# attenuator_evb.net
KiCad netlist of a schematic drawn in EasyEDA Pro
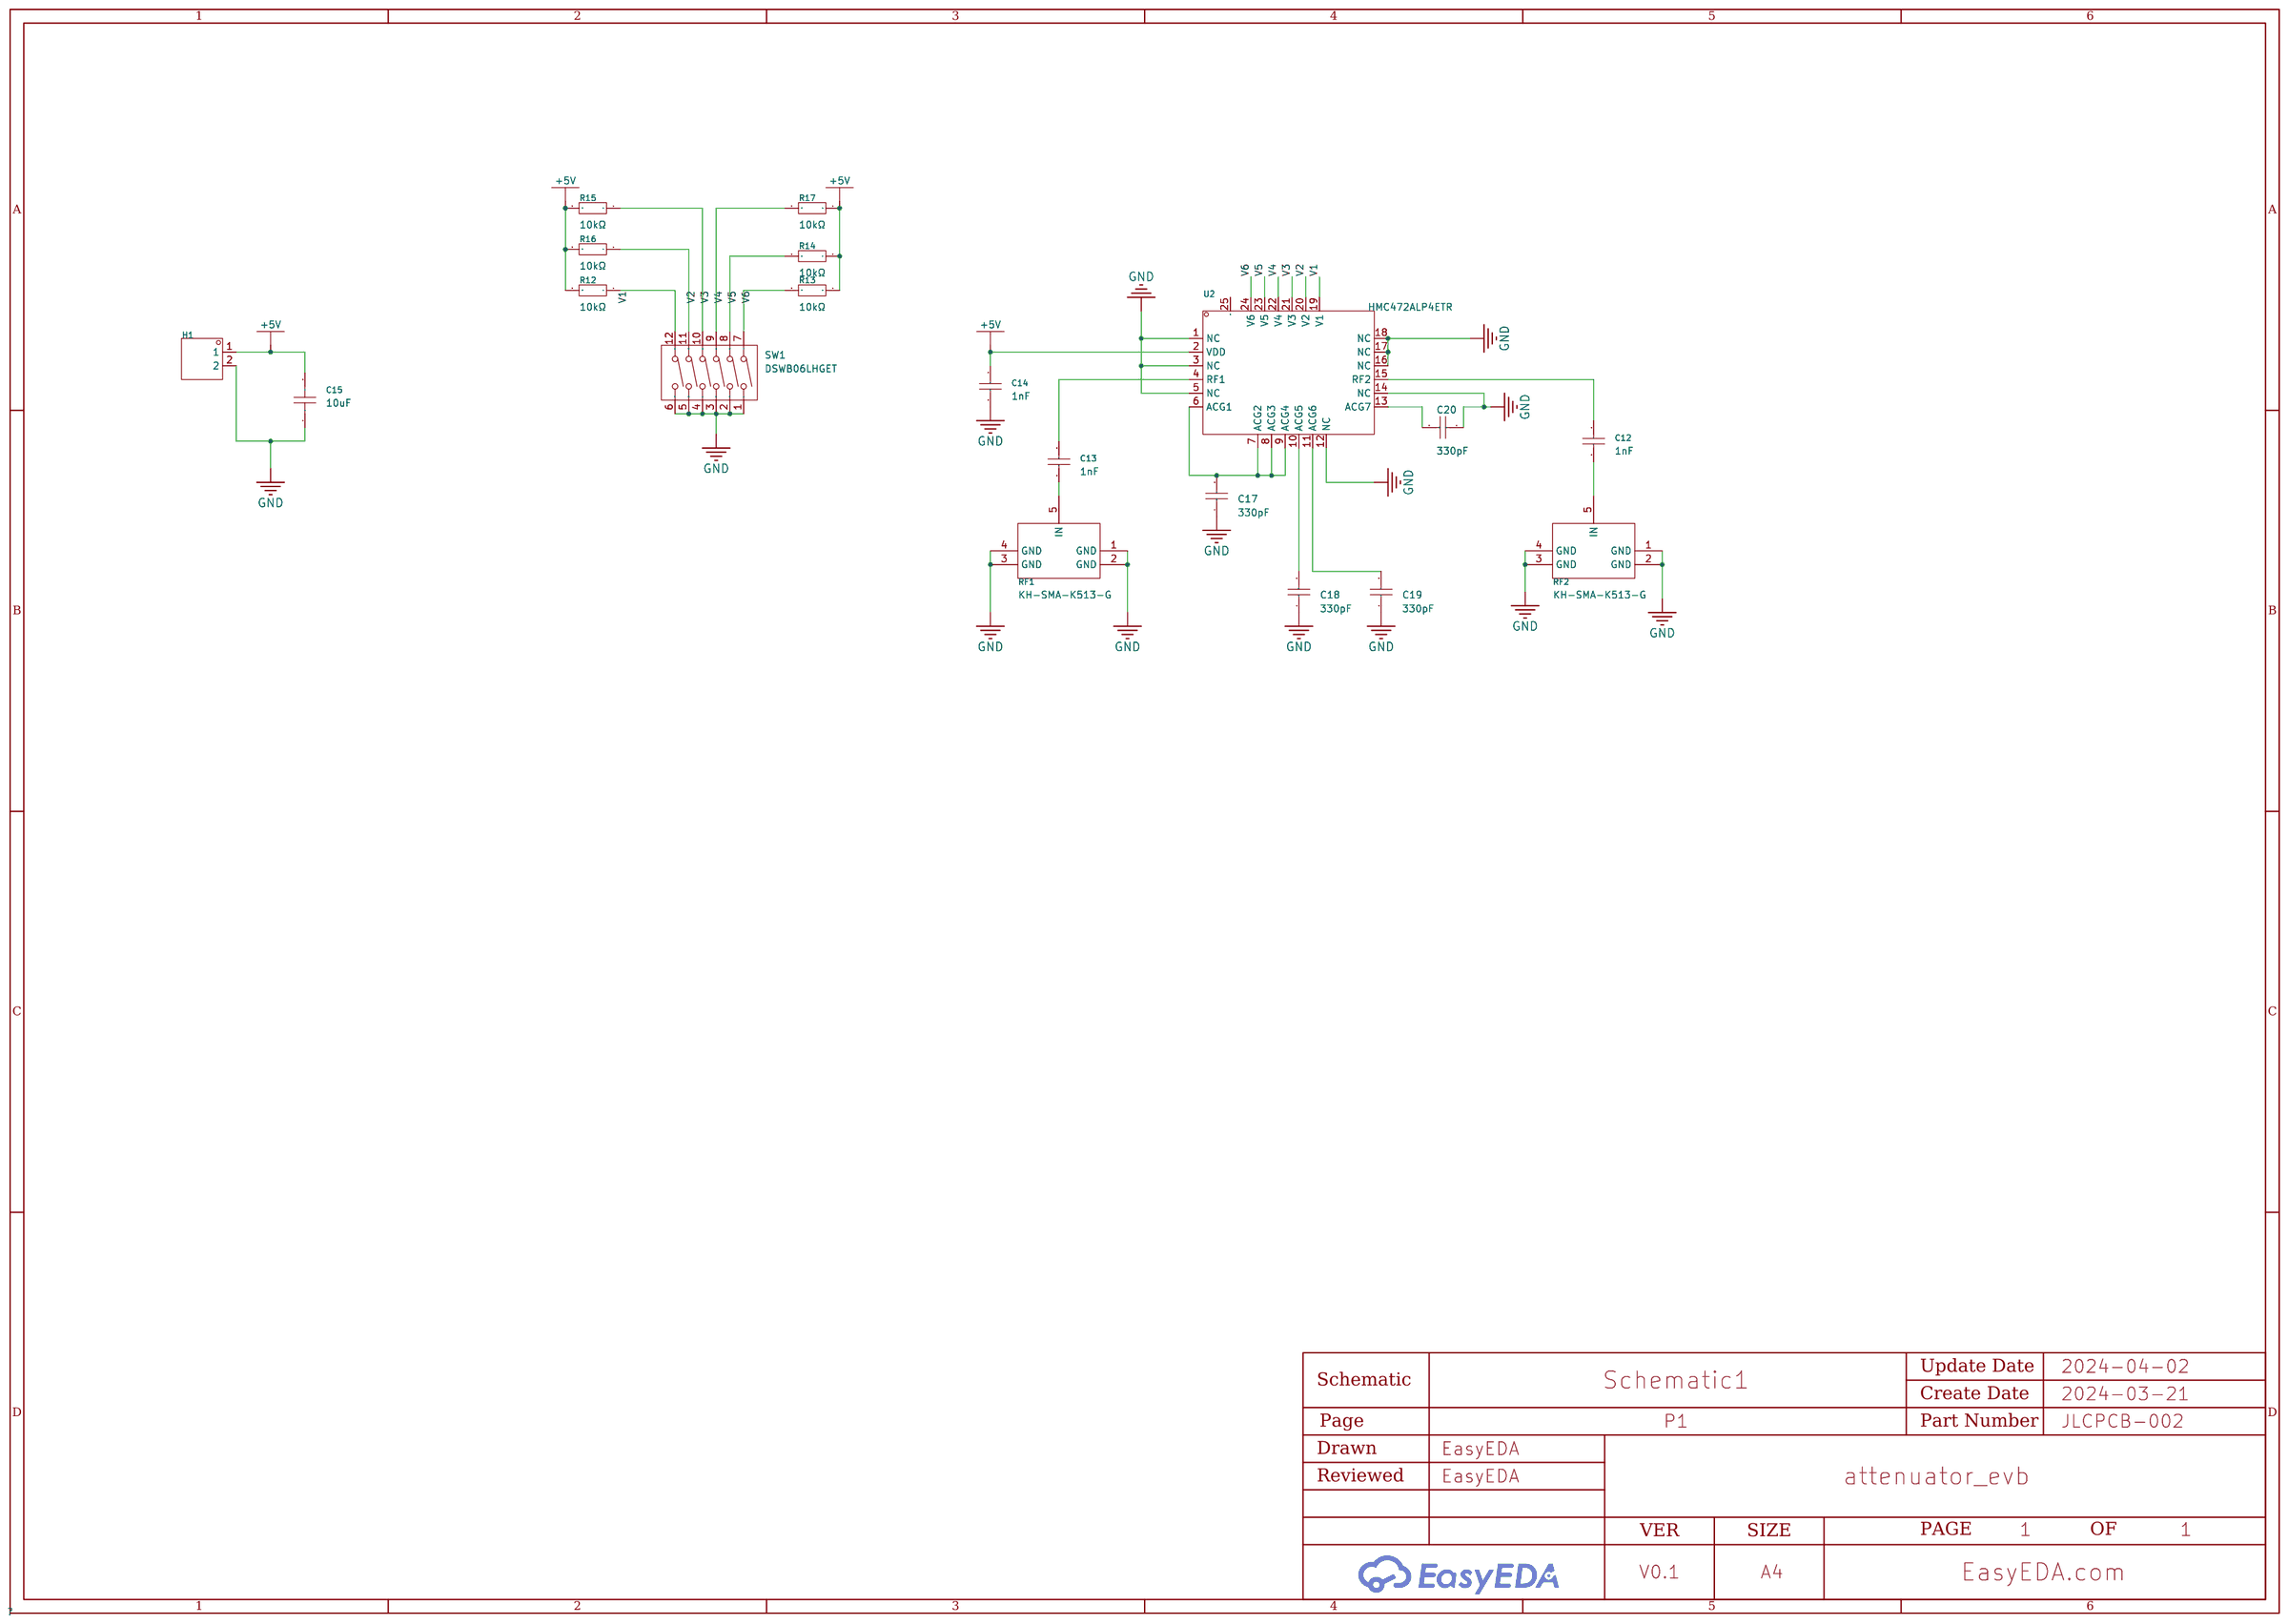
[diagram p0: schematic sheet]

(export (version "E")
  (design (tool "Eeschema 10.0.6"))
  (components
    (comp (ref "C12")
      (value "1nF")
      (footprint "easyedapro:C0402")
      (fields
        (field (name "Manufacturer Part") "CC0402KRX7R9BB102")
        (field (name "Manufacturer") "YAGEO(国巨)")
      )
      (libsource (lib "easyedapro") (part "CC0402KRX7R9BB102"))
    )
    (comp (ref "C13")
      (value "1nF")
      (footprint "easyedapro:C0402")
      (fields
        (field (name "Manufacturer Part") "CC0402KRX7R9BB102")
        (field (name "Manufacturer") "YAGEO(国巨)")
      )
      (libsource (lib "easyedapro") (part "CC0402KRX7R9BB102"))
    )
    (comp (ref "C14")
      (value "1nF")
      (footprint "easyedapro:C0402")
      (fields
        (field (name "Manufacturer Part") "CC0402KRX7R9BB102")
        (field (name "Manufacturer") "YAGEO(国巨)")
      )
      (libsource (lib "easyedapro") (part "CC0402KRX7R9BB102"))
    )
    (comp (ref "C15")
      (value "10uF")
      (footprint "easyedapro:C0603")
      (fields
        (field (name "Manufacturer Part") "CL10A106MP8NNNC")
        (field (name "Manufacturer") "SAMSUNG(三星)")
      )
      (libsource (lib "easyedapro") (part "CL10A106MP8NNNC"))
    )
    (comp (ref "C17")
      (value "330pF")
      (footprint "easyedapro:C0603")
      (fields (field (name "Manufacturer Part") "0603B331K500NT") (field (name "Manufacturer") "FH(风华)"))
      (libsource (lib "easyedapro") (part "0603B331K500NT"))
    )
    (comp (ref "C18")
      (value "330pF")
      (footprint "easyedapro:C0603")
      (fields (field (name "Manufacturer Part") "0603B331K500NT") (field (name "Manufacturer") "FH(风华)"))
      (libsource (lib "easyedapro") (part "0603B331K500NT"))
    )
    (comp (ref "C19")
      (value "330pF")
      (footprint "easyedapro:C0603")
      (fields (field (name "Manufacturer Part") "0603B331K500NT") (field (name "Manufacturer") "FH(风华)"))
      (libsource (lib "easyedapro") (part "0603B331K500NT"))
    )
    (comp (ref "C20")
      (value "330pF")
      (footprint "easyedapro:C0603")
      (fields (field (name "Manufacturer Part") "0603B331K500NT") (field (name "Manufacturer") "FH(风华)"))
      (libsource (lib "easyedapro") (part "0603B331K500NT"))
    )
    (comp (ref "H1")
      (value "~")
      (footprint "easyedapro:HDR-TH_2P-P2.54-V-M-1")
      (libsource (lib "easyedapro") (part "210S-1*2P L=11.6MMGold-plated black"))
    )
    (comp (ref "R12")
      (value "10kΩ")
      (footprint "easyedapro:R0603")
      (fields
        (field (name "Manufacturer Part") "0603WAF1002T5E")
        (field (name "Manufacturer") "UNI-ROYAL(厚声)")
      )
      (libsource (lib "easyedapro") (part "0603WAF1002T5E"))
    )
    (comp (ref "R13")
      (value "10kΩ")
      (footprint "easyedapro:R0603")
      (fields
        (field (name "Manufacturer Part") "0603WAF1002T5E")
        (field (name "Manufacturer") "UNI-ROYAL(厚声)")
      )
      (libsource (lib "easyedapro") (part "0603WAF1002T5E"))
    )
    (comp (ref "R14")
      (value "10kΩ")
      (footprint "easyedapro:R0603")
      (fields
        (field (name "Manufacturer Part") "0603WAF1002T5E")
        (field (name "Manufacturer") "UNI-ROYAL(厚声)")
      )
      (libsource (lib "easyedapro") (part "0603WAF1002T5E"))
    )
    (comp (ref "R15")
      (value "10kΩ")
      (footprint "easyedapro:R0603")
      (fields
        (field (name "Manufacturer Part") "0603WAF1002T5E")
        (field (name "Manufacturer") "UNI-ROYAL(厚声)")
      )
      (libsource (lib "easyedapro") (part "0603WAF1002T5E"))
    )
    (comp (ref "R16")
      (value "10kΩ")
      (footprint "easyedapro:R0603")
      (fields
        (field (name "Manufacturer Part") "0603WAF1002T5E")
        (field (name "Manufacturer") "UNI-ROYAL(厚声)")
      )
      (libsource (lib "easyedapro") (part "0603WAF1002T5E"))
    )
    (comp (ref "R17")
      (value "10kΩ")
      (footprint "easyedapro:R0603")
      (fields
        (field (name "Manufacturer Part") "0603WAF1002T5E")
        (field (name "Manufacturer") "UNI-ROYAL(厚声)")
      )
      (libsource (lib "easyedapro") (part "0603WAF1002T5E"))
    )
    (comp (ref "RF1")
      (value "KH-SMA-K513-G")
      (footprint "easyedapro:ANT-TH_KH-SMA-K513-G")
      (fields (field (name "Manufacturer") "kinghelm(金航标)"))
      (libsource (lib "easyedapro") (part "KH-SMA-K513-G"))
    )
    (comp (ref "RF2")
      (value "KH-SMA-K513-G")
      (footprint "easyedapro:ANT-TH_KH-SMA-K513-G")
      (fields (field (name "Manufacturer") "kinghelm(金航标)"))
      (libsource (lib "easyedapro") (part "KH-SMA-K513-G"))
    )
    (comp (ref "SW1")
      (value "DSWB06LHGET")
      (footprint "easyedapro:SW-TH_DSWB06LHGET")
      (description "Type:平拨,凸起式 Circuit:SPST Number of Positions:6Bit Lead Pitch:2.54mm Operating Life:- Color:Red")
      (fields (field (name "Manufacturer") "YE"))
      (libsource (lib "easyedapro") (part "DSWB06LHGET"))
    )
    (comp (ref "U2")
      (value "HMC472ALP4ETR")
      (footprint "easyedapro:QFN-24_L4.0-W4.0-P0.50-TL-EP2.7")
      (fields (field (name "Manufacturer") "ADI(亚德诺)"))
      (libsource (lib "easyedapro") (part "HMC472ALP4ETR"))
    )
  )
  (nets
    (net (code "1") (name "+5V") (class "Default")
      (node (ref "C14") (pin "2") (pinfunction "2_2") (pintype "input"))
      (node (ref "C15") (pin "2") (pinfunction "2_2") (pintype "input"))
      (node (ref "H1") (pin "1") (pinfunction "1_1") (pintype "input"))
      (node (ref "R12") (pin "2") (pinfunction "2_2") (pintype "input"))
      (node (ref "R13") (pin "1") (pinfunction "1_1") (pintype "input"))
      (node (ref "R14") (pin "1") (pinfunction "1_1") (pintype "input"))
      (node (ref "R15") (pin "2") (pinfunction "2_2") (pintype "input"))
      (node (ref "R16") (pin "2") (pinfunction "2_2") (pintype "input"))
      (node (ref "R17") (pin "1") (pinfunction "1_1") (pintype "input"))
      (node (ref "U2") (pin "2") (pinfunction "VDD_2") (pintype "input"))
    )
    (net (code "2") (name "/V1") (class "Default")
      (node (ref "R12") (pin "1") (pinfunction "1_1") (pintype "input"))
      (node (ref "SW1") (pin "12") (pinfunction "12_12") (pintype "unspecified"))
      (node (ref "U2") (pin "19") (pinfunction "V1_19") (pintype "input"))
    )
    (net (code "3") (name "/V2") (class "Default")
      (node (ref "R16") (pin "1") (pinfunction "1_1") (pintype "input"))
      (node (ref "SW1") (pin "11") (pinfunction "11_11") (pintype "unspecified"))
      (node (ref "U2") (pin "20") (pinfunction "V2_20") (pintype "input"))
    )
    (net (code "4") (name "/V3") (class "Default")
      (node (ref "R15") (pin "1") (pinfunction "1_1") (pintype "input"))
      (node (ref "SW1") (pin "10") (pinfunction "10_10") (pintype "unspecified"))
      (node (ref "U2") (pin "21") (pinfunction "V3_21") (pintype "input"))
    )
    (net (code "5") (name "/V4") (class "Default")
      (node (ref "R17") (pin "2") (pinfunction "2_2") (pintype "input"))
      (node (ref "SW1") (pin "9") (pinfunction "9_9") (pintype "unspecified"))
      (node (ref "U2") (pin "22") (pinfunction "V4_22") (pintype "input"))
    )
    (net (code "6") (name "/V5") (class "Default")
      (node (ref "R14") (pin "2") (pinfunction "2_2") (pintype "input"))
      (node (ref "SW1") (pin "8") (pinfunction "8_8") (pintype "unspecified"))
      (node (ref "U2") (pin "23") (pinfunction "V5_23") (pintype "input"))
    )
    (net (code "7") (name "/V6") (class "Default")
      (node (ref "R13") (pin "2") (pinfunction "2_2") (pintype "input"))
      (node (ref "SW1") (pin "7") (pinfunction "7_7") (pintype "unspecified"))
      (node (ref "U2") (pin "24") (pinfunction "V6_24") (pintype "input"))
    )
    (net (code "8") (name "GND") (class "Default")
      (node (ref "C14") (pin "1") (pinfunction "1_1") (pintype "input"))
      (node (ref "C15") (pin "1") (pinfunction "1_1") (pintype "input"))
      (node (ref "C17") (pin "1") (pinfunction "1_1") (pintype "input"))
      (node (ref "C18") (pin "1") (pinfunction "1_1") (pintype "input"))
      (node (ref "C19") (pin "1") (pinfunction "1_1") (pintype "input"))
      (node (ref "C20") (pin "1") (pinfunction "1_1") (pintype "input"))
      (node (ref "H1") (pin "2") (pinfunction "2_2") (pintype "input"))
      (node (ref "RF1") (pin "1") (pinfunction "GND_1") (pintype "input"))
      (node (ref "RF1") (pin "2") (pinfunction "GND_2") (pintype "input"))
      (node (ref "RF1") (pin "3") (pinfunction "GND_3") (pintype "input"))
      (node (ref "RF1") (pin "4") (pinfunction "GND_4") (pintype "input"))
      (node (ref "RF2") (pin "1") (pinfunction "GND_1") (pintype "input"))
      (node (ref "RF2") (pin "2") (pinfunction "GND_2") (pintype "input"))
      (node (ref "RF2") (pin "3") (pinfunction "GND_3") (pintype "input"))
      (node (ref "RF2") (pin "4") (pinfunction "GND_4") (pintype "input"))
      (node (ref "SW1") (pin "1") (pinfunction "1_1") (pintype "unspecified"))
      (node (ref "SW1") (pin "2") (pinfunction "2_2") (pintype "unspecified"))
      (node (ref "SW1") (pin "3") (pinfunction "3_3") (pintype "unspecified"))
      (node (ref "SW1") (pin "4") (pinfunction "4_4") (pintype "unspecified"))
      (node (ref "SW1") (pin "5") (pinfunction "5_5") (pintype "unspecified"))
      (node (ref "SW1") (pin "6") (pinfunction "6_6") (pintype "unspecified"))
      (node (ref "U2") (pin "1") (pinfunction "NC_1") (pintype "input"))
      (node (ref "U2") (pin "12") (pinfunction "NC_12") (pintype "input"))
      (node (ref "U2") (pin "14") (pinfunction "NC_14") (pintype "input"))
      (node (ref "U2") (pin "16") (pinfunction "NC_16") (pintype "input"))
      (node (ref "U2") (pin "17") (pinfunction "NC_17") (pintype "input"))
      (node (ref "U2") (pin "18") (pinfunction "NC_18") (pintype "input"))
      (node (ref "U2") (pin "3") (pinfunction "NC_3") (pintype "input"))
      (node (ref "U2") (pin "5") (pinfunction "NC_5") (pintype "input"))
    )
    (net (code "9") (name "Net-(RF1-IN)") (class "Default")
      (node (ref "C13") (pin "1") (pinfunction "1_1") (pintype "input"))
      (node (ref "RF1") (pin "5") (pinfunction "IN_5") (pintype "input"))
    )
    (net (code "10") (name "Net-(RF2-IN)") (class "Default")
      (node (ref "C12") (pin "1") (pinfunction "1_1") (pintype "input"))
      (node (ref "RF2") (pin "5") (pinfunction "IN_5") (pintype "input"))
    )
    (net (code "11") (name "Net-(U2-ACG1)") (class "Default")
      (node (ref "C17") (pin "2") (pinfunction "2_2") (pintype "input"))
      (node (ref "U2") (pin "6") (pinfunction "ACG1_6") (pintype "input"))
      (node (ref "U2") (pin "7") (pinfunction "ACG2_7") (pintype "input"))
      (node (ref "U2") (pin "8") (pinfunction "ACG3_8") (pintype "input"))
      (node (ref "U2") (pin "9") (pinfunction "ACG4_9") (pintype "input"))
    )
    (net (code "12") (name "Net-(U2-ACG5)") (class "Default")
      (node (ref "C18") (pin "2") (pinfunction "2_2") (pintype "input"))
      (node (ref "U2") (pin "10") (pinfunction "ACG5_10") (pintype "input"))
    )
    (net (code "13") (name "Net-(U2-ACG6)") (class "Default")
      (node (ref "C19") (pin "2") (pinfunction "2_2") (pintype "input"))
      (node (ref "U2") (pin "11") (pinfunction "ACG6_11") (pintype "input"))
    )
    (net (code "14") (name "Net-(U2-ACG7)") (class "Default")
      (node (ref "C20") (pin "2") (pinfunction "2_2") (pintype "input"))
      (node (ref "U2") (pin "13") (pinfunction "ACG7_13") (pintype "input"))
    )
    (net (code "15") (name "Net-(U2-RF1)") (class "Default")
      (node (ref "C13") (pin "2") (pinfunction "2_2") (pintype "input"))
      (node (ref "U2") (pin "4") (pinfunction "RF1_4") (pintype "input"))
    )
    (net (code "16") (name "Net-(U2-RF2)") (class "Default")
      (node (ref "C12") (pin "2") (pinfunction "2_2") (pintype "input"))
      (node (ref "U2") (pin "15") (pinfunction "RF2_15") (pintype "input"))
    )
    (net (code "17") (name "unconnected-(U2-Pad25)") (class "Default")
      (node (ref "U2") (pin "25") (pinfunction "25_25") (pintype "input"))
    )
  )
)
